# commu.net
KiCad netlist of a schematic drawn in Altium Designer
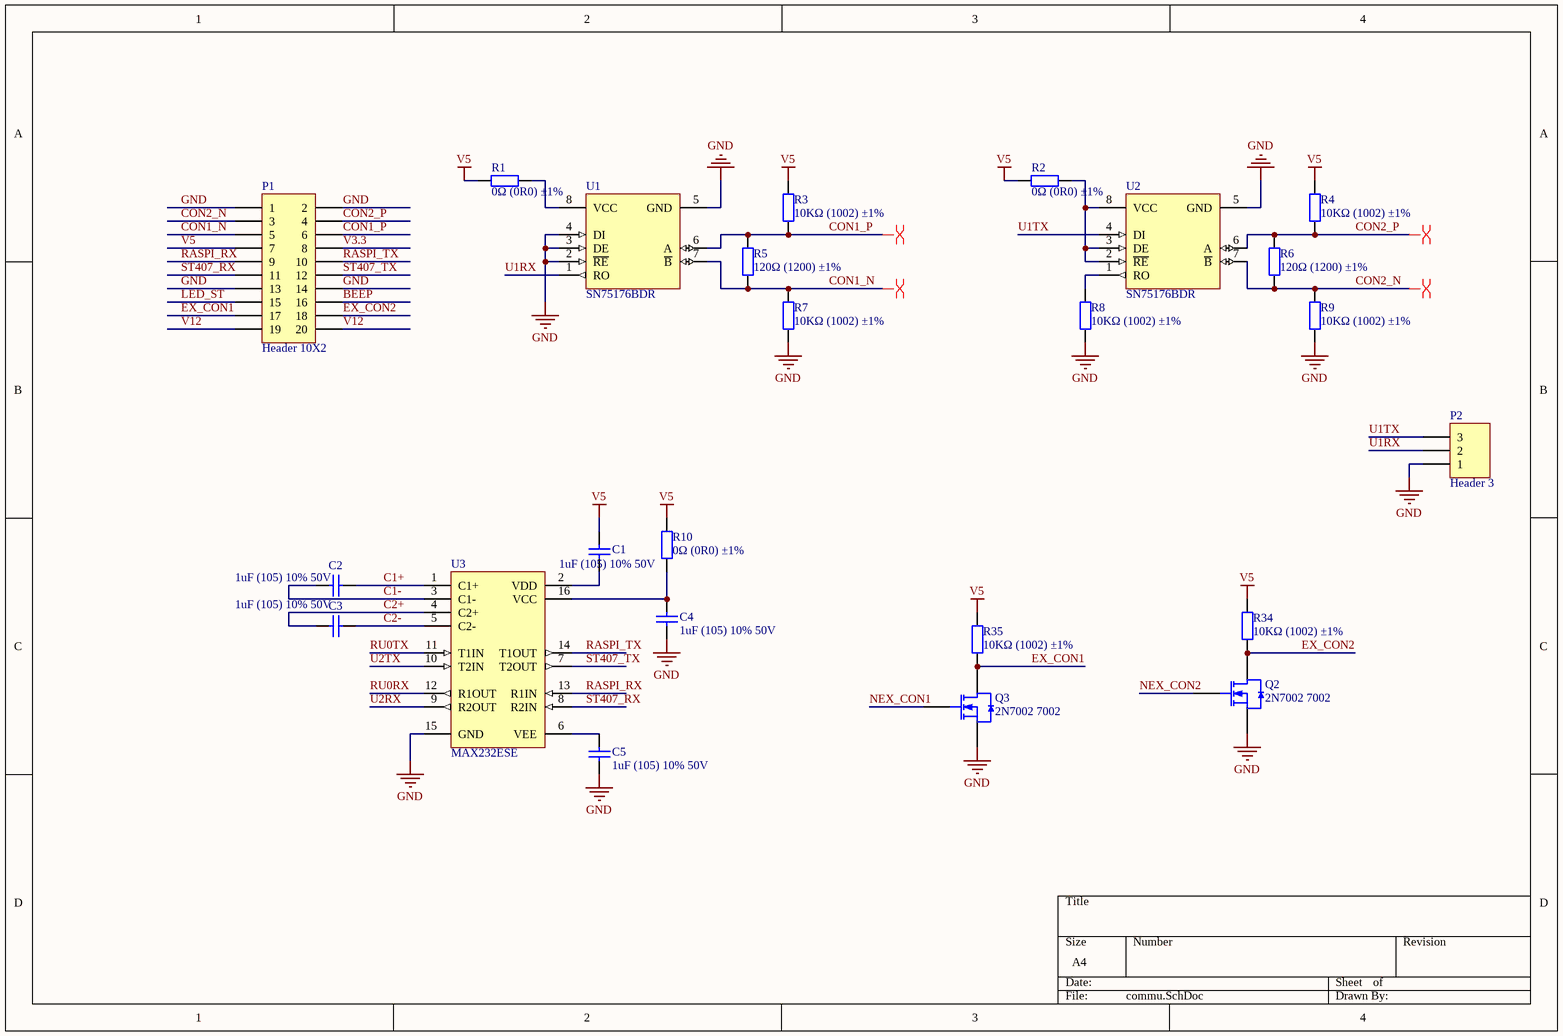
[diagram p0: commu.SchDoc]

(export (version "E")
  (design (tool "Eeschema 10.0.6"))
  (components
    (comp (ref "C1")
      (value "1uF (105) 10% 50V")
      (footprint "0603_C")
      (description "贴片电容")
      (libsource (lib "Miscellaneous Devices LC") (part "0603 1uF (105) 10% 50V"))
    )
    (comp (ref "C2")
      (value "1uF (105) 10% 50V")
      (footprint "0603_C")
      (description "贴片电容")
      (libsource (lib "Miscellaneous Devices LC") (part "0603 1uF (105) 10% 50V"))
    )
    (comp (ref "C3")
      (value "1uF (105) 10% 50V")
      (footprint "0603_C")
      (description "贴片电容")
      (libsource (lib "Miscellaneous Devices LC") (part "0603 1uF (105) 10% 50V"))
    )
    (comp (ref "C4")
      (value "1uF (105) 10% 50V")
      (footprint "0603_C")
      (description "贴片电容")
      (libsource (lib "Miscellaneous Devices LC") (part "0603 1uF (105) 10% 50V"))
    )
    (comp (ref "C5")
      (value "1uF (105) 10% 50V")
      (footprint "0603_C")
      (description "贴片电容")
      (libsource (lib "Miscellaneous Devices LC") (part "0603 1uF (105) 10% 50V"))
    )
    (comp (ref "P1")
      (value "Header 10X2")
      (footprint "HDR2X10")
      (description "Header, 10-Pin, Dual row")
      (fields (field (name "PUBLISHER") "Altium Limited"))
      (libsource (lib "Miscellaneous Connectors") (part "Header 10X2"))
    )
    (comp (ref "P2")
      (value "Header 3")
      (footprint "HDR1X3")
      (description "Header, 3-Pin")
      (fields (field (name "PUBLISHER") "Altium Limited"))
      (libsource (lib "Miscellaneous Connectors") (part "Header 3"))
    )
    (comp (ref "Q2")
      (value "2N7002 7002")
      (footprint "SOT-23(SOT-23-3)")
      (description "MOS(场效应管)")
      (libsource (lib "Miscellaneous Devices LC") (part "2N7002 7002"))
    )
    (comp (ref "Q3")
      (value "2N7002 7002")
      (footprint "SOT-23(SOT-23-3)")
      (description "MOS(场效应管)")
      (libsource (lib "Miscellaneous Devices LC") (part "2N7002 7002"))
    )
    (comp (ref "R1")
      (value "0Ω (0R0) ±1%")
      (footprint "1206_R")
      (description "贴片电阻")
      (libsource (lib "Miscellaneous Devices LC") (part "1206 0Ω (0R0) 1%"))
    )
    (comp (ref "R2")
      (value "0Ω (0R0) ±1%")
      (footprint "1206_R")
      (description "贴片电阻")
      (libsource (lib "Miscellaneous Devices LC") (part "1206 0Ω (0R0) 1%"))
    )
    (comp (ref "R3")
      (value "10KΩ (1002) ±1%")
      (footprint "0603_R")
      (description "贴片电阻")
      (libsource (lib "Miscellaneous Devices LC") (part "0603 10KΩ (1002) 1%"))
    )
    (comp (ref "R4")
      (value "10KΩ (1002) ±1%")
      (footprint "0603_R")
      (description "贴片电阻")
      (libsource (lib "Miscellaneous Devices LC") (part "0603 10KΩ (1002) 1%"))
    )
    (comp (ref "R5")
      (value "120Ω (1200) ±1%")
      (footprint "0603_R")
      (description "贴片电阻")
      (libsource (lib "Miscellaneous Devices LC") (part "0603 120Ω (1200) 1%"))
    )
    (comp (ref "R6")
      (value "120Ω (1200) ±1%")
      (footprint "0603_R")
      (description "贴片电阻")
      (libsource (lib "Miscellaneous Devices LC") (part "0603 120Ω (1200) 1%"))
    )
    (comp (ref "R7")
      (value "10KΩ (1002) ±1%")
      (footprint "0603_R")
      (description "贴片电阻")
      (libsource (lib "Miscellaneous Devices LC") (part "0603 10KΩ (1002) 1%"))
    )
    (comp (ref "R8")
      (value "10KΩ (1002) ±1%")
      (footprint "0603_R")
      (description "贴片电阻")
      (libsource (lib "Miscellaneous Devices LC") (part "0603 10KΩ (1002) 1%"))
    )
    (comp (ref "R9")
      (value "10KΩ (1002) ±1%")
      (footprint "0603_R")
      (description "贴片电阻")
      (libsource (lib "Miscellaneous Devices LC") (part "0603 10KΩ (1002) 1%"))
    )
    (comp (ref "R10")
      (value "0Ω (0R0) ±1%")
      (footprint "1206_R")
      (description "贴片电阻")
      (libsource (lib "") (part "1206 0Ω (0R0) 1%_1"))
    )
    (comp (ref "R34")
      (value "10KΩ (1002) ±1%")
      (footprint "0603_R")
      (description "贴片电阻")
      (libsource (lib "Miscellaneous Devices LC") (part "0603 10KΩ (1002) 1%"))
    )
    (comp (ref "R35")
      (value "10KΩ (1002) ±1%")
      (footprint "0603_R")
      (description "贴片电阻")
      (libsource (lib "Miscellaneous Devices LC") (part "0603 10KΩ (1002) 1%"))
    )
    (comp (ref "U1")
      (value "SN75176BDR")
      (footprint "SOIC-8_150mil")
      (description "RS-485/RS-422")
      (libsource (lib "Miscellaneous Devices LC") (part "SN75176BDR_[C7063]"))
    )
    (comp (ref "U2")
      (value "SN75176BDR")
      (footprint "SOIC-8_150mil")
      (description "RS-485/RS-422")
      (libsource (lib "Miscellaneous Devices LC") (part "SN75176BDR_[C7063]"))
    )
    (comp (ref "U3")
      (value "MAX232ESE")
      (footprint "SOIC-16_150mil")
      (description "RS232")
      (libsource (lib "Miscellaneous Devices LC") (part "MAX232ESE_[C26860]"))
    )
  )
  (nets
    (net (code "1") (name "/BEEP") (class "Default")
      (node (ref "P1") (pin "16") (pinfunction "16_16") (pintype "passive"))
    )
    (net (code "2") (name "/C1+") (class "Default")
      (node (ref "C2") (pin "2") (pinfunction "2_2") (pintype "passive"))
      (node (ref "U3") (pin "1") (pinfunction "C1+_1") (pintype "passive"))
    )
    (net (code "3") (name "/C1-") (class "Default")
      (node (ref "C2") (pin "1") (pinfunction "1_1") (pintype "passive"))
      (node (ref "U3") (pin "3") (pinfunction "C1-_3") (pintype "passive"))
    )
    (net (code "4") (name "/C2+") (class "Default")
      (node (ref "C3") (pin "1") (pinfunction "1_1") (pintype "passive"))
      (node (ref "U3") (pin "4") (pinfunction "C2+_4") (pintype "passive"))
    )
    (net (code "5") (name "/C2-") (class "Default")
      (node (ref "C3") (pin "2") (pinfunction "2_2") (pintype "passive"))
      (node (ref "U3") (pin "5") (pinfunction "C2-_5") (pintype "passive"))
    )
    (net (code "6") (name "/CON1_N") (class "Default")
      (node (ref "P1") (pin "5") (pinfunction "5_5") (pintype "passive"))
      (node (ref "R5") (pin "1") (pinfunction "1_1") (pintype "passive"))
      (node (ref "R7") (pin "2") (pinfunction "2_2") (pintype "passive"))
      (node (ref "U1") (pin "7") (pinfunction "~{B}_7") (pintype "bidirectional"))
    )
    (net (code "7") (name "/CON1_P") (class "Default")
      (node (ref "P1") (pin "6") (pinfunction "6_6") (pintype "passive"))
      (node (ref "R3") (pin "1") (pinfunction "1_1") (pintype "passive"))
      (node (ref "R5") (pin "2") (pinfunction "2_2") (pintype "passive"))
      (node (ref "U1") (pin "6") (pinfunction "A_6") (pintype "bidirectional"))
    )
    (net (code "8") (name "/CON2_N") (class "Default")
      (node (ref "P1") (pin "3") (pinfunction "3_3") (pintype "passive"))
      (node (ref "R6") (pin "1") (pinfunction "1_1") (pintype "passive"))
      (node (ref "R9") (pin "2") (pinfunction "2_2") (pintype "passive"))
      (node (ref "U2") (pin "7") (pinfunction "~{B}_7") (pintype "bidirectional"))
    )
    (net (code "9") (name "/CON2_P") (class "Default")
      (node (ref "P1") (pin "4") (pinfunction "4_4") (pintype "passive"))
      (node (ref "R4") (pin "1") (pinfunction "1_1") (pintype "passive"))
      (node (ref "R6") (pin "2") (pinfunction "2_2") (pintype "passive"))
      (node (ref "U2") (pin "6") (pinfunction "A_6") (pintype "bidirectional"))
    )
    (net (code "10") (name "/EX_CON1") (class "Default")
      (node (ref "P1") (pin "17") (pinfunction "17_17") (pintype "passive"))
      (node (ref "Q3") (pin "3") (pinfunction "D_3") (pintype "passive"))
      (node (ref "R35") (pin "1") (pinfunction "1_1") (pintype "passive"))
    )
    (net (code "11") (name "/EX_CON2") (class "Default")
      (node (ref "P1") (pin "18") (pinfunction "18_18") (pintype "passive"))
      (node (ref "Q2") (pin "3") (pinfunction "D_3") (pintype "passive"))
      (node (ref "R34") (pin "1") (pinfunction "1_1") (pintype "passive"))
    )
    (net (code "12") (name "/LED_ST") (class "Default")
      (node (ref "P1") (pin "15") (pinfunction "15_15") (pintype "passive"))
    )
    (net (code "13") (name "/NEX_CON1") (class "Default")
      (node (ref "Q3") (pin "1") (pinfunction "G_1") (pintype "passive"))
    )
    (net (code "14") (name "/NEX_CON2") (class "Default")
      (node (ref "Q2") (pin "1") (pinfunction "G_1") (pintype "passive"))
    )
    (net (code "15") (name "/RASPI_RX") (class "Default")
      (node (ref "P1") (pin "9") (pinfunction "9_9") (pintype "passive"))
      (node (ref "U3") (pin "13") (pinfunction "R1IN_13") (pintype "input"))
    )
    (net (code "16") (name "/RASPI_TX") (class "Default")
      (node (ref "P1") (pin "10") (pinfunction "10_10") (pintype "passive"))
      (node (ref "U3") (pin "14") (pinfunction "T1OUT_14") (pintype "output"))
    )
    (net (code "17") (name "/RU0RX") (class "Default")
      (node (ref "U3") (pin "12") (pinfunction "R1OUT_12") (pintype "output"))
    )
    (net (code "18") (name "/RU0TX") (class "Default")
      (node (ref "U3") (pin "11") (pinfunction "T1IN_11") (pintype "input"))
    )
    (net (code "19") (name "/ST407_RX") (class "Default")
      (node (ref "P1") (pin "11") (pinfunction "11_11") (pintype "passive"))
      (node (ref "U3") (pin "8") (pinfunction "R2IN_8") (pintype "input"))
    )
    (net (code "20") (name "/ST407_TX") (class "Default")
      (node (ref "P1") (pin "12") (pinfunction "12_12") (pintype "passive"))
      (node (ref "U3") (pin "7") (pinfunction "T2OUT_7") (pintype "output"))
    )
    (net (code "21") (name "/U1RX") (class "Default")
      (node (ref "P2") (pin "2") (pinfunction "2_2") (pintype "passive"))
      (node (ref "U1") (pin "1") (pinfunction "RO_1") (pintype "output"))
    )
    (net (code "22") (name "/U1TX") (class "Default")
      (node (ref "P2") (pin "3") (pinfunction "3_3") (pintype "passive"))
      (node (ref "U2") (pin "4") (pinfunction "DI_4") (pintype "input"))
    )
    (net (code "23") (name "/U2RX") (class "Default")
      (node (ref "U3") (pin "9") (pinfunction "R2OUT_9") (pintype "output"))
    )
    (net (code "24") (name "/U2TX") (class "Default")
      (node (ref "U3") (pin "10") (pinfunction "T2IN_10") (pintype "input"))
    )
    (net (code "25") (name "/V3.3") (class "Default")
      (node (ref "P1") (pin "8") (pinfunction "8_8") (pintype "passive"))
    )
    (net (code "26") (name "/V12") (class "Default")
      (node (ref "P1") (pin "19") (pinfunction "19_19") (pintype "passive"))
      (node (ref "P1") (pin "20") (pinfunction "20_20") (pintype "passive"))
    )
    (net (code "27") (name "GND") (class "Default")
      (node (ref "C4") (pin "1") (pinfunction "1_1") (pintype "passive"))
      (node (ref "C5") (pin "1") (pinfunction "1_1") (pintype "passive"))
      (node (ref "P1") (pin "1") (pinfunction "1_1") (pintype "passive"))
      (node (ref "P1") (pin "13") (pinfunction "13_13") (pintype "passive"))
      (node (ref "P1") (pin "14") (pinfunction "14_14") (pintype "passive"))
      (node (ref "P1") (pin "2") (pinfunction "2_2") (pintype "passive"))
      (node (ref "P2") (pin "1") (pinfunction "1_1") (pintype "passive"))
      (node (ref "Q2") (pin "2") (pinfunction "S_2") (pintype "passive"))
      (node (ref "Q3") (pin "2") (pinfunction "S_2") (pintype "passive"))
      (node (ref "R7") (pin "1") (pinfunction "1_1") (pintype "passive"))
      (node (ref "R8") (pin "1") (pinfunction "1_1") (pintype "passive"))
      (node (ref "R9") (pin "1") (pinfunction "1_1") (pintype "passive"))
      (node (ref "U1") (pin "2") (pinfunction "~{RE}_2") (pintype "input"))
      (node (ref "U1") (pin "3") (pinfunction "DE_3") (pintype "input"))
      (node (ref "U1") (pin "4") (pinfunction "DI_4") (pintype "input"))
      (node (ref "U1") (pin "5") (pinfunction "GND_5") (pintype "power_in"))
      (node (ref "U2") (pin "5") (pinfunction "GND_5") (pintype "power_in"))
      (node (ref "U3") (pin "15") (pinfunction "GND_15") (pintype "power_in"))
    )
    (net (code "28") (name "Net-(U1-VCC)") (class "Default")
      (node (ref "R1") (pin "2") (pinfunction "2_2") (pintype "passive"))
      (node (ref "U1") (pin "8") (pinfunction "VCC_8") (pintype "power_in"))
    )
    (net (code "29") (name "Net-(U2-DE)") (class "Default")
      (node (ref "R2") (pin "2") (pinfunction "2_2") (pintype "passive"))
      (node (ref "U2") (pin "2") (pinfunction "~{RE}_2") (pintype "input"))
      (node (ref "U2") (pin "3") (pinfunction "DE_3") (pintype "input"))
      (node (ref "U2") (pin "8") (pinfunction "VCC_8") (pintype "power_in"))
    )
    (net (code "30") (name "Net-(U2-RO)") (class "Default")
      (node (ref "R8") (pin "2") (pinfunction "2_2") (pintype "passive"))
      (node (ref "U2") (pin "1") (pinfunction "RO_1") (pintype "output"))
    )
    (net (code "31") (name "Net-(U3-VCC)") (class "Default")
      (node (ref "C4") (pin "2") (pinfunction "2_2") (pintype "passive"))
      (node (ref "R10") (pin "1") (pinfunction "1_1") (pintype "passive"))
      (node (ref "U3") (pin "16") (pinfunction "VCC_16") (pintype "power_in"))
    )
    (net (code "32") (name "Net-(U3-VDD)") (class "Default")
      (node (ref "C1") (pin "1") (pinfunction "1_1") (pintype "passive"))
      (node (ref "U3") (pin "2") (pinfunction "VDD_2") (pintype "power_in"))
    )
    (net (code "33") (name "Net-(U3-VEE)") (class "Default")
      (node (ref "C5") (pin "2") (pinfunction "2_2") (pintype "passive"))
      (node (ref "U3") (pin "6") (pinfunction "VEE_6") (pintype "power_in"))
    )
    (net (code "34") (name "V5") (class "Default")
      (node (ref "C1") (pin "2") (pinfunction "2_2") (pintype "passive"))
      (node (ref "P1") (pin "7") (pinfunction "7_7") (pintype "passive"))
      (node (ref "R1") (pin "1") (pinfunction "1_1") (pintype "passive"))
      (node (ref "R10") (pin "2") (pinfunction "2_2") (pintype "passive"))
      (node (ref "R2") (pin "1") (pinfunction "1_1") (pintype "passive"))
      (node (ref "R3") (pin "2") (pinfunction "2_2") (pintype "passive"))
      (node (ref "R34") (pin "2") (pinfunction "2_2") (pintype "passive"))
      (node (ref "R35") (pin "2") (pinfunction "2_2") (pintype "passive"))
      (node (ref "R4") (pin "2") (pinfunction "2_2") (pintype "passive"))
    )
  )
)
